# electricity-meter-wifi.net
KiCad netlist of a schematic drawn in EAGLE
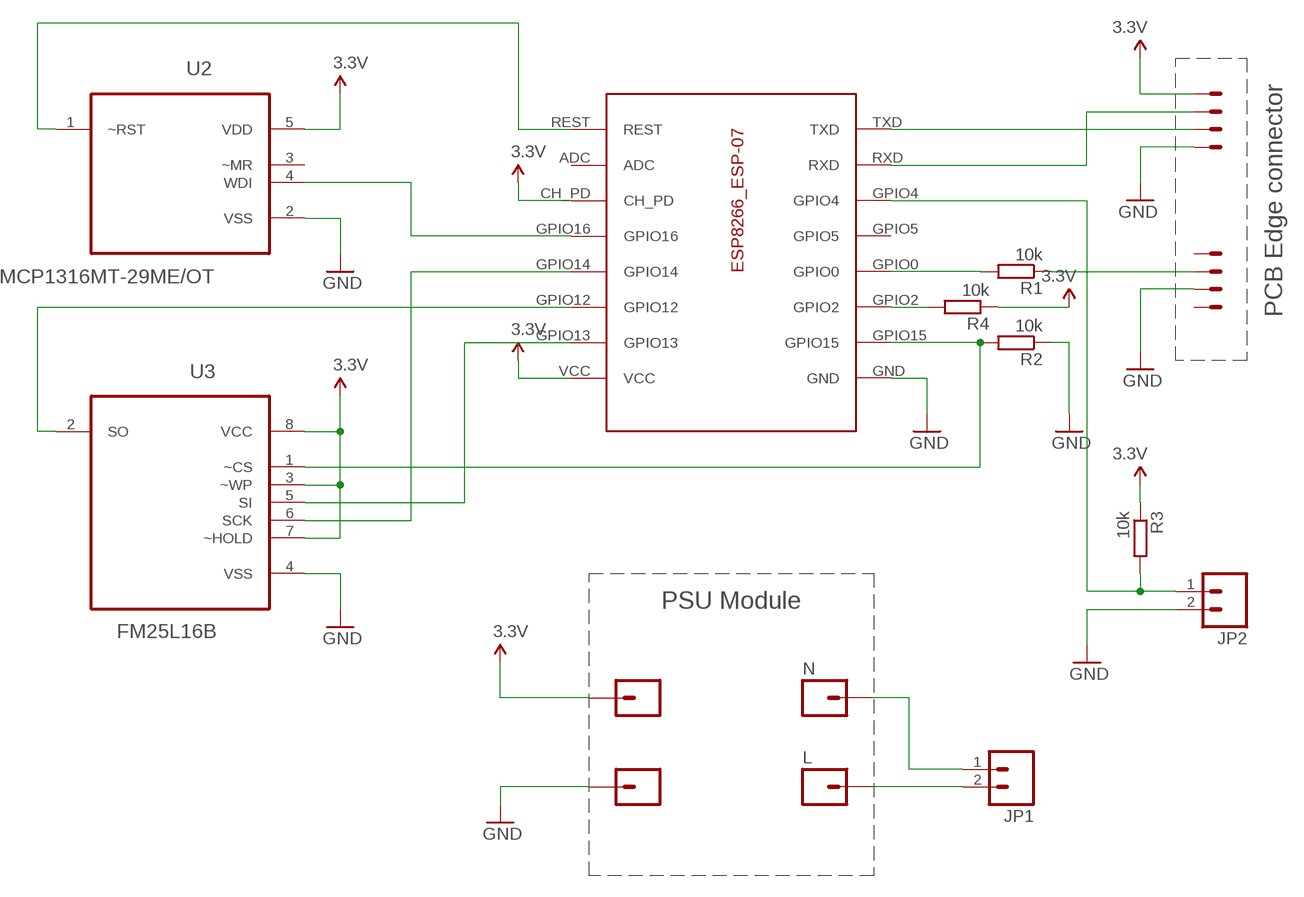
[diagram p0: schematic, sheet 1]

(export (version "E")
  (design (tool "Eeschema 10.0.6"))
  (components
    (comp (ref "3.3V")
      (value "M01PTH_2MM")
      (footprint "eagle-import:1X01_2MM")
      (libsource (lib "eagle-import") (part "M01PTH_2MM"))
    )
    (comp (ref "ESP8266_ESP-07")
      (value "ESP8266-07")
      (footprint "eagle-import:ESP-07")
      (libsource (lib "eagle-import") (part "ESP8266-07"))
    )
    (comp (ref "GND")
      (value "M01PTH_2MM")
      (footprint "eagle-import:1X01_2MM")
      (libsource (lib "eagle-import") (part "M01PTH_2MM"))
    )
    (comp (ref "JP1")
      (value "M02PTH3_5MM")
      (footprint "eagle-import:1X02_LONGPADS")
      (libsource (lib "eagle-import") (part "M02PTH3_5MM"))
    )
    (comp (ref "JP2")
      (value "M02PTH3_5MM")
      (footprint "eagle-import:1X02_LONGPADS")
      (libsource (lib "eagle-import") (part "M02PTH3_5MM"))
    )
    (comp (ref "L")
      (value "M01PTH_2MM")
      (footprint "eagle-import:1X01_2MM")
      (libsource (lib "eagle-import") (part "M01PTH_2MM"))
    )
    (comp (ref "N")
      (value "M01PTH_2MM")
      (footprint "eagle-import:1X01_2MM")
      (libsource (lib "eagle-import") (part "M01PTH_2MM"))
    )
    (comp (ref "R1")
      (value "10k")
      (footprint "eagle-import:R0805")
      (libsource (lib "eagle-import") (part "R-EU_R0805"))
    )
    (comp (ref "R2")
      (value "10k")
      (footprint "eagle-import:R0805")
      (libsource (lib "eagle-import") (part "R-EU_R0805"))
    )
    (comp (ref "R3")
      (value "10k")
      (footprint "eagle-import:R0805")
      (libsource (lib "eagle-import") (part "R-EU_R0805"))
    )
    (comp (ref "R4")
      (value "10k")
      (footprint "eagle-import:R0805")
      (libsource (lib "eagle-import") (part "R-EU_R0805"))
    )
    (comp (ref "U$1")
      (value "CON-PCB-SLOT-0.05MINIMAL")
      (footprint "eagle-import:CONN_SLOT_MINIMAL")
      (libsource (lib "eagle-import") (part "CON-PCB-SLOT-0.05MINIMAL"))
    )
    (comp (ref "U2")
      (value "MCP1316MT-29ME/OT")
      (footprint "eagle-import:SOT95P270X145-5N")
      (fields (field (name "MPN") "MCP1316T-29LE/OT"))
      (libsource (lib "eagle-import") (part "MCP1316T-29LE/OT"))
    )
    (comp (ref "U3")
      (value "FM25L16B")
      (footprint "eagle-import:SOIC127P600X175-8N")
      (fields (field (name "MPN") "25AA020A-I/SN"))
      (libsource (lib "eagle-import") (part "25AA020A-I/SN"))
    )
  )
  (nets
    (net (code "1") (name "3.3V") (class "Default")
      (node (ref "3.3V") (pin "1") (pinfunction "1_1") (pintype "passive"))
      (node (ref "ESP8266_ESP-07") (pin "CH_PD") (pinfunction "CH_PD_CH_PD") (pintype "bidirectional"))
      (node (ref "ESP8266_ESP-07") (pin "VCC") (pinfunction "VCC_VCC") (pintype "bidirectional"))
      (node (ref "R3") (pin "1") (pinfunction "1_1") (pintype "passive"))
      (node (ref "R4") (pin "1") (pinfunction "1_1") (pintype "passive"))
      (node (ref "U$1") (pin "4") (pinfunction "S_4") (pintype "passive"))
      (node (ref "U2") (pin "5") (pinfunction "VDD_5") (pintype "power_in"))
      (node (ref "U3") (pin "3") (pinfunction "~{WP}_3") (pintype "input"))
      (node (ref "U3") (pin "7") (pinfunction "~{HOLD}_7") (pintype "input"))
      (node (ref "U3") (pin "8") (pinfunction "VCC_8") (pintype "power_in"))
    )
    (net (code "2") (name "GND") (class "Default")
      (node (ref "ESP8266_ESP-07") (pin "GND") (pinfunction "GND_GND") (pintype "power_in"))
      (node (ref "GND") (pin "1") (pinfunction "1_1") (pintype "passive"))
      (node (ref "JP2") (pin "2") (pinfunction "2_2") (pintype "passive"))
      (node (ref "R2") (pin "1") (pinfunction "1_1") (pintype "passive"))
      (node (ref "U$1") (pin "1") (pinfunction "S_1") (pintype "passive"))
      (node (ref "U$1") (pin "7") (pinfunction "S_7") (pintype "passive"))
      (node (ref "U2") (pin "2") (pinfunction "VSS_2") (pintype "power_in"))
      (node (ref "U3") (pin "4") (pinfunction "VSS_4") (pintype "power_in"))
    )
    (net (code "3") (name "Net-(ESP8266_ESP-07-PadGPIO0)") (class "Default")
      (node (ref "ESP8266_ESP-07") (pin "GPIO0") (pinfunction "GPIO0_GPIO0") (pintype "bidirectional"))
      (node (ref "R1") (pin "2") (pinfunction "2_2") (pintype "passive"))
    )
    (net (code "4") (name "Net-(ESP8266_ESP-07-PadGPIO2)") (class "Default")
      (node (ref "ESP8266_ESP-07") (pin "GPIO2") (pinfunction "GPIO2_GPIO2") (pintype "bidirectional"))
      (node (ref "R4") (pin "2") (pinfunction "2_2") (pintype "passive"))
    )
    (net (code "5") (name "Net-(ESP8266_ESP-07-PadGPIO4)") (class "Default")
      (node (ref "ESP8266_ESP-07") (pin "GPIO4") (pinfunction "GPIO4_GPIO4") (pintype "bidirectional"))
      (node (ref "JP2") (pin "1") (pinfunction "1_1") (pintype "passive"))
      (node (ref "R3") (pin "2") (pinfunction "2_2") (pintype "passive"))
    )
    (net (code "6") (name "Net-(JP1-Pad1)") (class "Default")
      (node (ref "JP1") (pin "1") (pinfunction "1_1") (pintype "passive"))
      (node (ref "N") (pin "1") (pinfunction "1_1") (pintype "passive"))
    )
    (net (code "7") (name "Net-(JP1-Pad2)") (class "Default")
      (node (ref "JP1") (pin "2") (pinfunction "2_2") (pintype "passive"))
      (node (ref "L") (pin "1") (pinfunction "1_1") (pintype "passive"))
    )
    (net (code "8") (name "Net-(U$1B-S)") (class "Default")
      (node (ref "ESP8266_ESP-07") (pin "TXD") (pinfunction "TXD_TXD") (pintype "bidirectional"))
      (node (ref "U$1") (pin "2") (pinfunction "S_2") (pintype "passive"))
    )
    (net (code "9") (name "Net-(U$1C-S)") (class "Default")
      (node (ref "ESP8266_ESP-07") (pin "RXD") (pinfunction "RXD_RXD") (pintype "bidirectional"))
      (node (ref "U$1") (pin "3") (pinfunction "S_3") (pintype "passive"))
    )
    (net (code "10") (name "Net-(U$1F-S)") (class "Default")
      (node (ref "R1") (pin "1") (pinfunction "1_1") (pintype "passive"))
      (node (ref "U$1") (pin "6") (pinfunction "S_6") (pintype "passive"))
    )
    (net (code "11") (name "Net-(U2-WDI)") (class "Default")
      (node (ref "ESP8266_ESP-07") (pin "GPIO16") (pinfunction "GPIO16_GPIO16") (pintype "bidirectional"))
      (node (ref "U2") (pin "4") (pinfunction "WDI_4") (pintype "input"))
    )
    (net (code "12") (name "Net-(U2-~{RST})") (class "Default")
      (node (ref "ESP8266_ESP-07") (pin "REST") (pinfunction "REST_REST") (pintype "bidirectional"))
      (node (ref "U2") (pin "1") (pinfunction "~{RST}_1") (pintype "output"))
    )
    (net (code "13") (name "Net-(U3-SCK)") (class "Default")
      (node (ref "ESP8266_ESP-07") (pin "GPIO14") (pinfunction "GPIO14_GPIO14") (pintype "bidirectional"))
      (node (ref "U3") (pin "6") (pinfunction "SCK_6") (pintype "input"))
    )
    (net (code "14") (name "Net-(U3-SI)") (class "Default")
      (node (ref "ESP8266_ESP-07") (pin "GPIO13") (pinfunction "GPIO13_GPIO13") (pintype "bidirectional"))
      (node (ref "U3") (pin "5") (pinfunction "SI_5") (pintype "input"))
    )
    (net (code "15") (name "Net-(U3-SO)") (class "Default")
      (node (ref "ESP8266_ESP-07") (pin "GPIO12") (pinfunction "GPIO12_GPIO12") (pintype "bidirectional"))
      (node (ref "U3") (pin "2") (pinfunction "SO_2") (pintype "output"))
    )
    (net (code "16") (name "Net-(U3-~{CS})") (class "Default")
      (node (ref "ESP8266_ESP-07") (pin "GPIO15") (pinfunction "GPIO15_GPIO15") (pintype "bidirectional"))
      (node (ref "R2") (pin "2") (pinfunction "2_2") (pintype "passive"))
      (node (ref "U3") (pin "1") (pinfunction "~{CS}_1") (pintype "input"))
    )
    (net (code "17") (name "unconnected-(ESP8266_ESP-07-PadADC)") (class "Default")
      (node (ref "ESP8266_ESP-07") (pin "ADC") (pinfunction "ADC_ADC") (pintype "bidirectional"))
    )
    (net (code "18") (name "unconnected-(ESP8266_ESP-07-PadGPIO5)") (class "Default")
      (node (ref "ESP8266_ESP-07") (pin "GPIO5") (pinfunction "GPIO5_GPIO5") (pintype "bidirectional"))
    )
    (net (code "19") (name "unconnected-(U$1E-S-Pad5)") (class "Default")
      (node (ref "U$1") (pin "5") (pinfunction "S_5") (pintype "passive"))
    )
    (net (code "20") (name "unconnected-(U$1H-S-Pad8)") (class "Default")
      (node (ref "U$1") (pin "8") (pinfunction "S_8") (pintype "passive"))
    )
    (net (code "21") (name "unconnected-(U2-~{MR}-Pad3)") (class "Default")
      (node (ref "U2") (pin "3") (pinfunction "~{MR}_3") (pintype "input"))
    )
  )
)
